# LVDS_IFC.net
KiCad netlist of a schematic drawn in Altium Designer
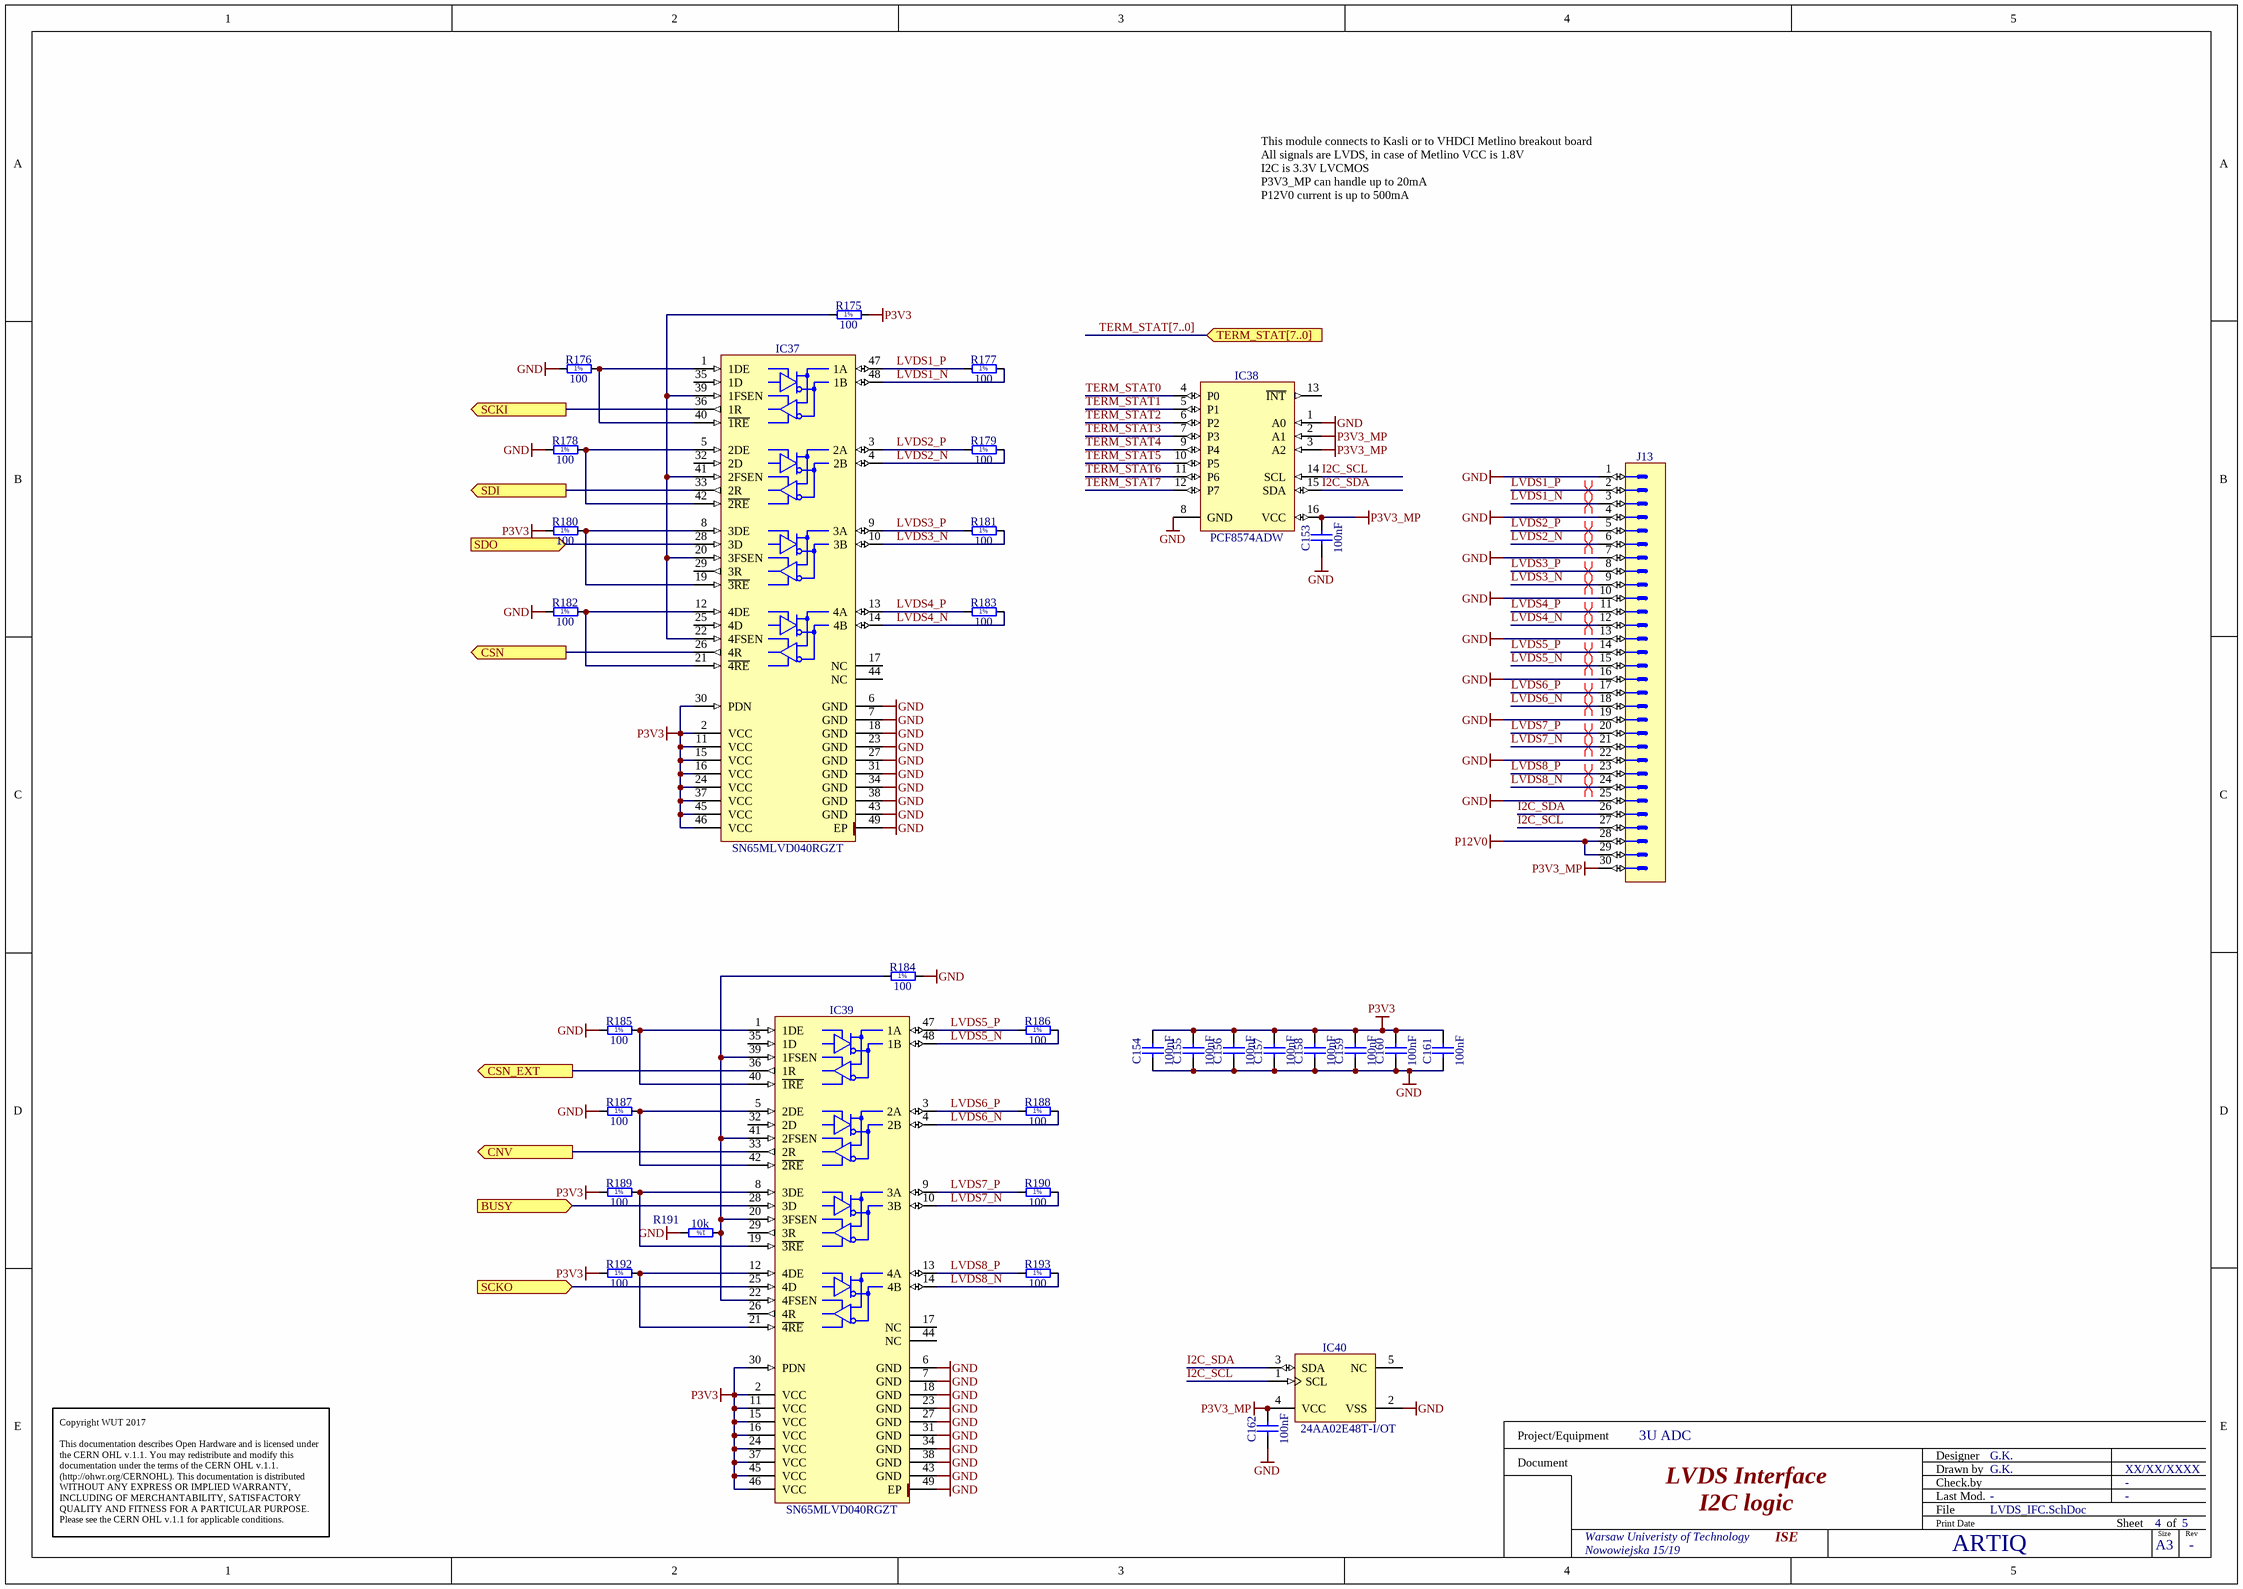
[diagram p0: LVDS_IFC.SchDoc]

(export (version "E")
  (design (tool "Eeschema 10.0.6"))
  (components
    (comp (ref "C153")
      (value "100nF")
      (footprint "CAPC1005X55N")
      (description "Non-polarised capacitor")
      (fields
        (field (name "PART NUMBER") "CC0402_100NF_16V_10%_X5R")
        (field (name "VOLTAGE") "16V")
        (field (name "AUTHOR") "CERN DEM JLC")
      )
      (libsource (lib "Capacitors") (part "Capacitor - non polarized"))
    )
    (comp (ref "C154")
      (value "100nF")
      (footprint "CAPC1005X55N")
      (description "Non-polarised capacitor")
      (fields
        (field (name "PART NUMBER") "CC0402_100NF_16V_10%_X5R")
        (field (name "VOLTAGE") "16V")
        (field (name "AUTHOR") "CERN DEM JLC")
      )
      (libsource (lib "Capacitors") (part "Capacitor - non polarized"))
    )
    (comp (ref "C155")
      (value "100nF")
      (footprint "CAPC1005X55N")
      (description "Non-polarised capacitor")
      (fields
        (field (name "PART NUMBER") "CC0402_100NF_16V_10%_X5R")
        (field (name "VOLTAGE") "16V")
        (field (name "AUTHOR") "CERN DEM JLC")
      )
      (libsource (lib "Capacitors") (part "Capacitor - non polarized"))
    )
    (comp (ref "C156")
      (value "100nF")
      (footprint "CAPC1005X55N")
      (description "Non-polarised capacitor")
      (fields
        (field (name "PART NUMBER") "CC0402_100NF_16V_10%_X5R")
        (field (name "VOLTAGE") "16V")
        (field (name "AUTHOR") "CERN DEM JLC")
      )
      (libsource (lib "Capacitors") (part "Capacitor - non polarized"))
    )
    (comp (ref "C157")
      (value "100nF")
      (footprint "CAPC1005X55N")
      (description "Non-polarised capacitor")
      (fields
        (field (name "PART NUMBER") "CC0402_100NF_16V_10%_X5R")
        (field (name "VOLTAGE") "16V")
        (field (name "AUTHOR") "CERN DEM JLC")
      )
      (libsource (lib "Capacitors") (part "Capacitor - non polarized"))
    )
    (comp (ref "C158")
      (value "100nF")
      (footprint "CAPC1005X55N")
      (description "Non-polarised capacitor")
      (fields
        (field (name "PART NUMBER") "CC0402_100NF_16V_10%_X5R")
        (field (name "VOLTAGE") "16V")
        (field (name "AUTHOR") "CERN DEM JLC")
      )
      (libsource (lib "Capacitors") (part "Capacitor - non polarized"))
    )
    (comp (ref "C159")
      (value "100nF")
      (footprint "CAPC1005X55N")
      (description "Non-polarised capacitor")
      (fields
        (field (name "PART NUMBER") "CC0402_100NF_16V_10%_X5R")
        (field (name "VOLTAGE") "16V")
        (field (name "AUTHOR") "CERN DEM JLC")
      )
      (libsource (lib "Capacitors") (part "Capacitor - non polarized"))
    )
    (comp (ref "C160")
      (value "100nF")
      (footprint "CAPC1005X55N")
      (description "Non-polarised capacitor")
      (fields
        (field (name "PART NUMBER") "CC0402_100NF_16V_10%_X5R")
        (field (name "VOLTAGE") "16V")
        (field (name "AUTHOR") "CERN DEM JLC")
      )
      (libsource (lib "Capacitors") (part "Capacitor - non polarized"))
    )
    (comp (ref "C161")
      (value "100nF")
      (footprint "CAPC1005X55N")
      (description "Non-polarised capacitor")
      (fields
        (field (name "PART NUMBER") "CC0402_100NF_16V_10%_X5R")
        (field (name "VOLTAGE") "16V")
        (field (name "AUTHOR") "CERN DEM JLC")
      )
      (libsource (lib "Capacitors") (part "Capacitor - non polarized"))
    )
    (comp (ref "C162")
      (value "100nF")
      (footprint "CAPC1005X55N")
      (description "Non-polarised capacitor")
      (fields
        (field (name "PART NUMBER") "CC0402_100NF_16V_10%_X5R")
        (field (name "VOLTAGE") "16V")
        (field (name "AUTHOR") "CERN DEM JLC")
      )
      (libsource (lib "Capacitors") (part "Capacitor - non polarized"))
    )
    (comp (ref "IC37")
      (value "SN65MLVD040RGZT")
      (footprint "QFN50P700X700X100-49N-S420")
      (description "4-Channel Half-Duplex M-LVDS Line Transceiver")
      (fields (field (name "MANUFACTURER") "TEXAS INSTRUMENTS") (field (name "AUTHOR") "CERN DEM JLC"))
      (libsource (lib "ICs And Semiconductors") (part "SN65MLVD040"))
    )
    (comp (ref "IC38")
      (value "PCF8574ADW")
      (footprint "SOIC127P1030X265-16N")
      (description "Remote 8-bit I/O Expander For I2C Bus")
      (fields (field (name "MANUFACTURER") "TEXAS INSTRUMENTS") (field (name "AUTHOR") "CERN DEM JLC"))
      (libsource (lib "ICs And Semiconductors") (part "PCF8574ADW"))
    )
    (comp (ref "IC39")
      (value "SN65MLVD040RGZT")
      (footprint "QFN50P700X700X100-49N-S420")
      (description "4-Channel Half-Duplex M-LVDS Line Transceiver")
      (fields (field (name "MANUFACTURER") "TEXAS INSTRUMENTS") (field (name "AUTHOR") "CERN DEM JLC"))
      (libsource (lib "ICs And Semiconductors") (part "SN65MLVD040"))
    )
    (comp (ref "IC40")
      (value "24AA02E48T-I/OT")
      (footprint "SOT95P280X145-5N")
      (description "1.7V-5.5V, 2K I2C Serial EEPROM With EUI-48 Node Identity")
      (fields (field (name "MANUFACTURER") "MICROCHIP TECHNOLOGY") (field (name "AUTHOR") "CERN DEM MR"))
      (libsource (lib "ICs And Semiconductors") (part "24AA02E48T-I/OT"))
    )
    (comp (ref "J13")
      (value "~")
      (footprint "3M_N2530-6002RB")
      (description "Connector 30 Male")
      (fields
        (field (name "PART NUMBER") "3M_N2530-6002RB")
        (field (name "MANUFACTURER") "3M")
        (field (name "AUTHOR") "CERN DEM JLC")
      )
      (libsource (lib "Connectors") (part "Connector 30 Male"))
    )
    (comp (ref "R175")
      (value "100")
      (footprint "RESC1005X40N")
      (description "Resistor - 1%")
      (fields
        (field (name "PART NUMBER") "R0402_100R_1%_0.1W_100PPM")
        (field (name "POWER") "0.1W")
        (field (name "AUTHOR") "CERN DEM JLC")
      )
      (libsource (lib "Resistors") (part "Resistor - 1%"))
    )
    (comp (ref "R176")
      (value "100")
      (footprint "RESC1005X40N")
      (description "Resistor - 1%")
      (fields
        (field (name "PART NUMBER") "R0402_100R_1%_0.1W_100PPM")
        (field (name "POWER") "0.1W")
        (field (name "AUTHOR") "CERN DEM JLC")
      )
      (libsource (lib "Resistors") (part "Resistor - 1%"))
    )
    (comp (ref "R177")
      (value "100")
      (footprint "RESC1005X40N")
      (description "Resistor - 1%")
      (fields
        (field (name "PART NUMBER") "R0402_100R_1%_0.1W_100PPM")
        (field (name "POWER") "0.1W")
        (field (name "AUTHOR") "CERN DEM JLC")
      )
      (libsource (lib "Resistors") (part "Resistor - 1%"))
    )
    (comp (ref "R178")
      (value "100")
      (footprint "RESC1005X40N")
      (description "Resistor - 1%")
      (fields
        (field (name "PART NUMBER") "R0402_100R_1%_0.1W_100PPM")
        (field (name "POWER") "0.1W")
        (field (name "AUTHOR") "CERN DEM JLC")
      )
      (libsource (lib "Resistors") (part "Resistor - 1%"))
    )
    (comp (ref "R179")
      (value "100")
      (footprint "RESC1005X40N")
      (description "Resistor - 1%")
      (fields
        (field (name "PART NUMBER") "R0402_100R_1%_0.1W_100PPM")
        (field (name "POWER") "0.1W")
        (field (name "AUTHOR") "CERN DEM JLC")
      )
      (libsource (lib "Resistors") (part "Resistor - 1%"))
    )
    (comp (ref "R180")
      (value "100")
      (footprint "RESC1005X40N")
      (description "Resistor - 1%")
      (fields
        (field (name "PART NUMBER") "R0402_100R_1%_0.1W_100PPM")
        (field (name "POWER") "0.1W")
        (field (name "AUTHOR") "CERN DEM JLC")
      )
      (libsource (lib "Resistors") (part "Resistor - 1%"))
    )
    (comp (ref "R181")
      (value "100")
      (footprint "RESC1005X40N")
      (description "Resistor - 1%")
      (fields
        (field (name "PART NUMBER") "R0402_100R_1%_0.1W_100PPM")
        (field (name "POWER") "0.1W")
        (field (name "AUTHOR") "CERN DEM JLC")
      )
      (libsource (lib "Resistors") (part "Resistor - 1%"))
    )
    (comp (ref "R182")
      (value "100")
      (footprint "RESC1005X40N")
      (description "Resistor - 1%")
      (fields
        (field (name "PART NUMBER") "R0402_100R_1%_0.1W_100PPM")
        (field (name "POWER") "0.1W")
        (field (name "AUTHOR") "CERN DEM JLC")
      )
      (libsource (lib "Resistors") (part "Resistor - 1%"))
    )
    (comp (ref "R183")
      (value "100")
      (footprint "RESC1005X40N")
      (description "Resistor - 1%")
      (fields
        (field (name "PART NUMBER") "R0402_100R_1%_0.1W_100PPM")
        (field (name "POWER") "0.1W")
        (field (name "AUTHOR") "CERN DEM JLC")
      )
      (libsource (lib "Resistors") (part "Resistor - 1%"))
    )
    (comp (ref "R184")
      (value "100")
      (footprint "RESC1005X40N")
      (description "Resistor - 1%")
      (fields
        (field (name "PART NUMBER") "R0402_100R_1%_0.1W_100PPM")
        (field (name "POWER") "0.1W")
        (field (name "AUTHOR") "CERN DEM JLC")
      )
      (libsource (lib "Resistors") (part "Resistor - 1%"))
    )
    (comp (ref "R185")
      (value "100")
      (footprint "RESC1005X40N")
      (description "Resistor - 1%")
      (fields
        (field (name "PART NUMBER") "R0402_100R_1%_0.1W_100PPM")
        (field (name "POWER") "0.1W")
        (field (name "AUTHOR") "CERN DEM JLC")
      )
      (libsource (lib "Resistors") (part "Resistor - 1%"))
    )
    (comp (ref "R186")
      (value "100")
      (footprint "RESC1005X40N")
      (description "Resistor - 1%")
      (fields
        (field (name "PART NUMBER") "R0402_100R_1%_0.1W_100PPM")
        (field (name "POWER") "0.1W")
        (field (name "AUTHOR") "CERN DEM JLC")
      )
      (libsource (lib "Resistors") (part "Resistor - 1%"))
    )
    (comp (ref "R187")
      (value "100")
      (footprint "RESC1005X40N")
      (description "Resistor - 1%")
      (fields
        (field (name "PART NUMBER") "R0402_100R_1%_0.1W_100PPM")
        (field (name "POWER") "0.1W")
        (field (name "AUTHOR") "CERN DEM JLC")
      )
      (libsource (lib "Resistors") (part "Resistor - 1%"))
    )
    (comp (ref "R188")
      (value "100")
      (footprint "RESC1005X40N")
      (description "Resistor - 1%")
      (fields
        (field (name "PART NUMBER") "R0402_100R_1%_0.1W_100PPM")
        (field (name "POWER") "0.1W")
        (field (name "AUTHOR") "CERN DEM JLC")
      )
      (libsource (lib "Resistors") (part "Resistor - 1%"))
    )
    (comp (ref "R189")
      (value "100")
      (footprint "RESC1005X40N")
      (description "Resistor - 1%")
      (fields
        (field (name "PART NUMBER") "R0402_100R_1%_0.1W_100PPM")
        (field (name "POWER") "0.1W")
        (field (name "AUTHOR") "CERN DEM JLC")
      )
      (libsource (lib "Resistors") (part "Resistor - 1%"))
    )
    (comp (ref "R190")
      (value "100")
      (footprint "RESC1005X40N")
      (description "Resistor - 1%")
      (fields
        (field (name "PART NUMBER") "R0402_100R_1%_0.1W_100PPM")
        (field (name "POWER") "0.1W")
        (field (name "AUTHOR") "CERN DEM JLC")
      )
      (libsource (lib "Resistors") (part "Resistor - 1%"))
    )
    (comp (ref "R191")
      (value "10k")
      (footprint "RESC1005X40N")
      (description "Resistor - 1%")
      (fields
        (field (name "PART NUMBER") "R0402_10K_1%_0.0625W_100PPM")
        (field (name "POWER") "0.0625W")
        (field (name "AUTHOR") "CERN DEM JLC")
      )
      (libsource (lib "Resistors") (part "Resistor - 1%"))
    )
    (comp (ref "R192")
      (value "100")
      (footprint "RESC1005X40N")
      (description "Resistor - 1%")
      (fields
        (field (name "PART NUMBER") "R0402_100R_1%_0.1W_100PPM")
        (field (name "POWER") "0.1W")
        (field (name "AUTHOR") "CERN DEM JLC")
      )
      (libsource (lib "Resistors") (part "Resistor - 1%"))
    )
    (comp (ref "R193")
      (value "100")
      (footprint "RESC1005X40N")
      (description "Resistor - 1%")
      (fields
        (field (name "PART NUMBER") "R0402_100R_1%_0.1W_100PPM")
        (field (name "POWER") "0.1W")
        (field (name "AUTHOR") "CERN DEM JLC")
      )
      (libsource (lib "Resistors") (part "Resistor - 1%"))
    )
  )
  (nets
    (net (code "1") (name "/BUSY") (class "Default")
      (node (ref "IC39") (pin "28") (pinfunction "3D_28") (pintype "input"))
    )
    (net (code "2") (name "/CNV") (class "Default")
      (node (ref "IC39") (pin "33") (pinfunction "2R_33") (pintype "output"))
    )
    (net (code "3") (name "/CSN") (class "Default")
      (node (ref "IC37") (pin "26") (pinfunction "4R_26") (pintype "output"))
    )
    (net (code "4") (name "/CSN_EXT") (class "Default")
      (node (ref "IC39") (pin "36") (pinfunction "1R_36") (pintype "output"))
    )
    (net (code "5") (name "/I2C_SCL") (class "Default")
      (node (ref "IC38") (pin "14") (pinfunction "SCL_14") (pintype "input"))
      (node (ref "IC40") (pin "1") (pinfunction "SCL_1") (pintype "input"))
      (node (ref "J13") (pin "27") (pinfunction "27_27") (pintype "bidirectional"))
    )
    (net (code "6") (name "/I2C_SDA") (class "Default")
      (node (ref "IC38") (pin "15") (pinfunction "SDA_15") (pintype "bidirectional"))
      (node (ref "IC40") (pin "3") (pinfunction "SDA_3") (pintype "bidirectional"))
      (node (ref "J13") (pin "26") (pinfunction "26_26") (pintype "bidirectional"))
    )
    (net (code "7") (name "/LVDS1_N") (class "Default")
      (node (ref "IC37") (pin "48") (pinfunction "1B_48") (pintype "bidirectional"))
      (node (ref "J13") (pin "3") (pinfunction "3_3") (pintype "bidirectional"))
      (node (ref "R177") (pin "2") (pinfunction "2_2") (pintype "passive"))
    )
    (net (code "8") (name "/LVDS1_P") (class "Default")
      (node (ref "IC37") (pin "47") (pinfunction "1A_47") (pintype "bidirectional"))
      (node (ref "J13") (pin "2") (pinfunction "2_2") (pintype "bidirectional"))
      (node (ref "R177") (pin "1") (pinfunction "1_1") (pintype "passive"))
    )
    (net (code "9") (name "/LVDS2_N") (class "Default")
      (node (ref "IC37") (pin "4") (pinfunction "2B_4") (pintype "bidirectional"))
      (node (ref "J13") (pin "6") (pinfunction "6_6") (pintype "bidirectional"))
      (node (ref "R179") (pin "2") (pinfunction "2_2") (pintype "passive"))
    )
    (net (code "10") (name "/LVDS2_P") (class "Default")
      (node (ref "IC37") (pin "3") (pinfunction "2A_3") (pintype "bidirectional"))
      (node (ref "J13") (pin "5") (pinfunction "5_5") (pintype "bidirectional"))
      (node (ref "R179") (pin "1") (pinfunction "1_1") (pintype "passive"))
    )
    (net (code "11") (name "/LVDS3_N") (class "Default")
      (node (ref "IC37") (pin "10") (pinfunction "3B_10") (pintype "bidirectional"))
      (node (ref "J13") (pin "9") (pinfunction "9_9") (pintype "bidirectional"))
      (node (ref "R181") (pin "2") (pinfunction "2_2") (pintype "passive"))
    )
    (net (code "12") (name "/LVDS3_P") (class "Default")
      (node (ref "IC37") (pin "9") (pinfunction "3A_9") (pintype "bidirectional"))
      (node (ref "J13") (pin "8") (pinfunction "8_8") (pintype "bidirectional"))
      (node (ref "R181") (pin "1") (pinfunction "1_1") (pintype "passive"))
    )
    (net (code "13") (name "/LVDS4_N") (class "Default")
      (node (ref "IC37") (pin "14") (pinfunction "4B_14") (pintype "bidirectional"))
      (node (ref "J13") (pin "12") (pinfunction "12_12") (pintype "bidirectional"))
      (node (ref "R183") (pin "2") (pinfunction "2_2") (pintype "passive"))
    )
    (net (code "14") (name "/LVDS4_P") (class "Default")
      (node (ref "IC37") (pin "13") (pinfunction "4A_13") (pintype "bidirectional"))
      (node (ref "J13") (pin "11") (pinfunction "11_11") (pintype "bidirectional"))
      (node (ref "R183") (pin "1") (pinfunction "1_1") (pintype "passive"))
    )
    (net (code "15") (name "/LVDS5_N") (class "Default")
      (node (ref "IC39") (pin "48") (pinfunction "1B_48") (pintype "bidirectional"))
      (node (ref "J13") (pin "15") (pinfunction "15_15") (pintype "bidirectional"))
      (node (ref "R186") (pin "2") (pinfunction "2_2") (pintype "passive"))
    )
    (net (code "16") (name "/LVDS5_P") (class "Default")
      (node (ref "IC39") (pin "47") (pinfunction "1A_47") (pintype "bidirectional"))
      (node (ref "J13") (pin "14") (pinfunction "14_14") (pintype "bidirectional"))
      (node (ref "R186") (pin "1") (pinfunction "1_1") (pintype "passive"))
    )
    (net (code "17") (name "/LVDS6_N") (class "Default")
      (node (ref "IC39") (pin "4") (pinfunction "2B_4") (pintype "bidirectional"))
      (node (ref "J13") (pin "18") (pinfunction "18_18") (pintype "bidirectional"))
      (node (ref "R188") (pin "2") (pinfunction "2_2") (pintype "passive"))
    )
    (net (code "18") (name "/LVDS6_P") (class "Default")
      (node (ref "IC39") (pin "3") (pinfunction "2A_3") (pintype "bidirectional"))
      (node (ref "J13") (pin "17") (pinfunction "17_17") (pintype "bidirectional"))
      (node (ref "R188") (pin "1") (pinfunction "1_1") (pintype "passive"))
    )
    (net (code "19") (name "/LVDS7_N") (class "Default")
      (node (ref "IC39") (pin "10") (pinfunction "3B_10") (pintype "bidirectional"))
      (node (ref "J13") (pin "21") (pinfunction "21_21") (pintype "bidirectional"))
      (node (ref "R190") (pin "2") (pinfunction "2_2") (pintype "passive"))
    )
    (net (code "20") (name "/LVDS7_P") (class "Default")
      (node (ref "IC39") (pin "9") (pinfunction "3A_9") (pintype "bidirectional"))
      (node (ref "J13") (pin "20") (pinfunction "20_20") (pintype "bidirectional"))
      (node (ref "R190") (pin "1") (pinfunction "1_1") (pintype "passive"))
    )
    (net (code "21") (name "/LVDS8_N") (class "Default")
      (node (ref "IC39") (pin "14") (pinfunction "4B_14") (pintype "bidirectional"))
      (node (ref "J13") (pin "24") (pinfunction "24_24") (pintype "bidirectional"))
      (node (ref "R193") (pin "2") (pinfunction "2_2") (pintype "passive"))
    )
    (net (code "22") (name "/LVDS8_P") (class "Default")
      (node (ref "IC39") (pin "13") (pinfunction "4A_13") (pintype "bidirectional"))
      (node (ref "J13") (pin "23") (pinfunction "23_23") (pintype "bidirectional"))
      (node (ref "R193") (pin "1") (pinfunction "1_1") (pintype "passive"))
    )
    (net (code "23") (name "/SCKI") (class "Default")
      (node (ref "IC37") (pin "36") (pinfunction "1R_36") (pintype "output"))
    )
    (net (code "24") (name "/SCKO") (class "Default")
      (node (ref "IC39") (pin "25") (pinfunction "4D_25") (pintype "input"))
    )
    (net (code "25") (name "/SDI") (class "Default")
      (node (ref "IC37") (pin "33") (pinfunction "2R_33") (pintype "output"))
    )
    (net (code "26") (name "/SDO") (class "Default")
      (node (ref "IC37") (pin "28") (pinfunction "3D_28") (pintype "input"))
    )
    (net (code "27") (name "/TERM_STAT0") (class "Default")
      (node (ref "IC38") (pin "4") (pinfunction "P0_4") (pintype "bidirectional"))
    )
    (net (code "28") (name "/TERM_STAT1") (class "Default")
      (node (ref "IC38") (pin "5") (pinfunction "P1_5") (pintype "bidirectional"))
    )
    (net (code "29") (name "/TERM_STAT2") (class "Default")
      (node (ref "IC38") (pin "6") (pinfunction "P2_6") (pintype "bidirectional"))
    )
    (net (code "30") (name "/TERM_STAT3") (class "Default")
      (node (ref "IC38") (pin "7") (pinfunction "P3_7") (pintype "bidirectional"))
    )
    (net (code "31") (name "/TERM_STAT4") (class "Default")
      (node (ref "IC38") (pin "9") (pinfunction "P4_9") (pintype "bidirectional"))
    )
    (net (code "32") (name "/TERM_STAT5") (class "Default")
      (node (ref "IC38") (pin "10") (pinfunction "P5_10") (pintype "bidirectional"))
    )
    (net (code "33") (name "/TERM_STAT6") (class "Default")
      (node (ref "IC38") (pin "11") (pinfunction "P6_11") (pintype "bidirectional"))
    )
    (net (code "34") (name "/TERM_STAT7") (class "Default")
      (node (ref "IC38") (pin "12") (pinfunction "P7_12") (pintype "bidirectional"))
    )
    (net (code "36") (name "GND") (class "Default")
      (node (ref "C153") (pin "1") (pinfunction "1_1") (pintype "passive"))
      (node (ref "C154") (pin "1") (pinfunction "1_1") (pintype "passive"))
      (node (ref "C155") (pin "1") (pinfunction "1_1") (pintype "passive"))
      (node (ref "C156") (pin "1") (pinfunction "1_1") (pintype "passive"))
      (node (ref "C157") (pin "1") (pinfunction "1_1") (pintype "passive"))
      (node (ref "C158") (pin "1") (pinfunction "1_1") (pintype "passive"))
      (node (ref "C159") (pin "1") (pinfunction "1_1") (pintype "passive"))
      (node (ref "C160") (pin "1") (pinfunction "1_1") (pintype "passive"))
      (node (ref "C161") (pin "1") (pinfunction "1_1") (pintype "passive"))
      (node (ref "C162") (pin "1") (pinfunction "1_1") (pintype "passive"))
      (node (ref "IC37") (pin "18") (pinfunction "GND_18") (pintype "power_in"))
      (node (ref "IC37") (pin "23") (pinfunction "GND_23") (pintype "power_in"))
      (node (ref "IC37") (pin "27") (pinfunction "GND_27") (pintype "power_in"))
      (node (ref "IC37") (pin "31") (pinfunction "GND_31") (pintype "power_in"))
      (node (ref "IC37") (pin "34") (pinfunction "GND_34") (pintype "power_in"))
      (node (ref "IC37") (pin "38") (pinfunction "GND_38") (pintype "power_in"))
      (node (ref "IC37") (pin "43") (pinfunction "GND_43") (pintype "power_in"))
      (node (ref "IC37") (pin "49") (pinfunction "EP_49") (pintype "power_in"))
      (node (ref "IC37") (pin "6") (pinfunction "GND_6") (pintype "power_in"))
      (node (ref "IC37") (pin "7") (pinfunction "GND_7") (pintype "power_in"))
      (node (ref "IC38") (pin "1") (pinfunction "A0_1") (pintype "input"))
      (node (ref "IC38") (pin "8") (pinfunction "GND_8") (pintype "power_in"))
      (node (ref "IC39") (pin "18") (pinfunction "GND_18") (pintype "power_in"))
      (node (ref "IC39") (pin "23") (pinfunction "GND_23") (pintype "power_in"))
      (node (ref "IC39") (pin "27") (pinfunction "GND_27") (pintype "power_in"))
      (node (ref "IC39") (pin "31") (pinfunction "GND_31") (pintype "power_in"))
      (node (ref "IC39") (pin "34") (pinfunction "GND_34") (pintype "power_in"))
      (node (ref "IC39") (pin "38") (pinfunction "GND_38") (pintype "power_in"))
      (node (ref "IC39") (pin "43") (pinfunction "GND_43") (pintype "power_in"))
      (node (ref "IC39") (pin "49") (pinfunction "EP_49") (pintype "power_in"))
      (node (ref "IC39") (pin "6") (pinfunction "GND_6") (pintype "power_in"))
      (node (ref "IC39") (pin "7") (pinfunction "GND_7") (pintype "power_in"))
      (node (ref "IC40") (pin "2") (pinfunction "VSS_2") (pintype "power_in"))
      (node (ref "J13") (pin "1") (pinfunction "1_1") (pintype "bidirectional"))
      (node (ref "J13") (pin "10") (pinfunction "10_10") (pintype "bidirectional"))
      (node (ref "J13") (pin "13") (pinfunction "13_13") (pintype "bidirectional"))
      (node (ref "J13") (pin "16") (pinfunction "16_16") (pintype "bidirectional"))
      (node (ref "J13") (pin "19") (pinfunction "19_19") (pintype "bidirectional"))
      (node (ref "J13") (pin "22") (pinfunction "22_22") (pintype "bidirectional"))
      (node (ref "J13") (pin "25") (pinfunction "25_25") (pintype "bidirectional"))
      (node (ref "J13") (pin "4") (pinfunction "4_4") (pintype "bidirectional"))
      (node (ref "J13") (pin "7") (pinfunction "7_7") (pintype "bidirectional"))
      (node (ref "R176") (pin "1") (pinfunction "1_1") (pintype "passive"))
      (node (ref "R178") (pin "1") (pinfunction "1_1") (pintype "passive"))
      (node (ref "R182") (pin "1") (pinfunction "1_1") (pintype "passive"))
      (node (ref "R184") (pin "2") (pinfunction "2_2") (pintype "passive"))
      (node (ref "R185") (pin "1") (pinfunction "1_1") (pintype "passive"))
      (node (ref "R187") (pin "1") (pinfunction "1_1") (pintype "passive"))
      (node (ref "R191") (pin "2") (pinfunction "2_2") (pintype "passive"))
    )
    (net (code "37") (name "Net-(IC37-1DE)") (class "Default")
      (node (ref "IC37") (pin "1") (pinfunction "1DE_1") (pintype "input"))
      (node (ref "IC37") (pin "40") (pinfunction "~{1RE}_40") (pintype "input"))
      (node (ref "R176") (pin "2") (pinfunction "2_2") (pintype "passive"))
    )
    (net (code "38") (name "Net-(IC37-1FSEN)") (class "Default")
      (node (ref "IC37") (pin "20") (pinfunction "3FSEN_20") (pintype "input"))
      (node (ref "IC37") (pin "22") (pinfunction "4FSEN_22") (pintype "input"))
      (node (ref "IC37") (pin "39") (pinfunction "1FSEN_39") (pintype "input"))
      (node (ref "IC37") (pin "41") (pinfunction "2FSEN_41") (pintype "input"))
      (node (ref "R175") (pin "1") (pinfunction "1_1") (pintype "passive"))
    )
    (net (code "39") (name "Net-(IC37-2DE)") (class "Default")
      (node (ref "IC37") (pin "42") (pinfunction "~{2RE}_42") (pintype "input"))
      (node (ref "IC37") (pin "5") (pinfunction "2DE_5") (pintype "input"))
      (node (ref "R178") (pin "2") (pinfunction "2_2") (pintype "passive"))
    )
    (net (code "40") (name "Net-(IC37-3DE)") (class "Default")
      (node (ref "IC37") (pin "19") (pinfunction "~{3RE}_19") (pintype "input"))
      (node (ref "IC37") (pin "8") (pinfunction "3DE_8") (pintype "input"))
      (node (ref "R180") (pin "2") (pinfunction "2_2") (pintype "passive"))
    )
    (net (code "41") (name "Net-(IC37-4DE)") (class "Default")
      (node (ref "IC37") (pin "12") (pinfunction "4DE_12") (pintype "input"))
      (node (ref "IC37") (pin "21") (pinfunction "~{4RE}_21") (pintype "input"))
      (node (ref "R182") (pin "2") (pinfunction "2_2") (pintype "passive"))
    )
    (net (code "42") (name "Net-(IC39-1DE)") (class "Default")
      (node (ref "IC39") (pin "1") (pinfunction "1DE_1") (pintype "input"))
      (node (ref "IC39") (pin "40") (pinfunction "~{1RE}_40") (pintype "input"))
      (node (ref "R185") (pin "2") (pinfunction "2_2") (pintype "passive"))
    )
    (net (code "43") (name "Net-(IC39-1FSEN)") (class "Default")
      (node (ref "IC39") (pin "20") (pinfunction "3FSEN_20") (pintype "input"))
      (node (ref "IC39") (pin "22") (pinfunction "4FSEN_22") (pintype "input"))
      (node (ref "IC39") (pin "39") (pinfunction "1FSEN_39") (pintype "input"))
      (node (ref "IC39") (pin "41") (pinfunction "2FSEN_41") (pintype "input"))
      (node (ref "R184") (pin "1") (pinfunction "1_1") (pintype "passive"))
      (node (ref "R191") (pin "1") (pinfunction "1_1") (pintype "passive"))
    )
    (net (code "44") (name "Net-(IC39-2DE)") (class "Default")
      (node (ref "IC39") (pin "42") (pinfunction "~{2RE}_42") (pintype "input"))
      (node (ref "IC39") (pin "5") (pinfunction "2DE_5") (pintype "input"))
      (node (ref "R187") (pin "2") (pinfunction "2_2") (pintype "passive"))
    )
    (net (code "45") (name "Net-(IC39-3DE)") (class "Default")
      (node (ref "IC39") (pin "19") (pinfunction "~{3RE}_19") (pintype "input"))
      (node (ref "IC39") (pin "8") (pinfunction "3DE_8") (pintype "input"))
      (node (ref "R189") (pin "2") (pinfunction "2_2") (pintype "passive"))
    )
    (net (code "46") (name "Net-(IC39-4DE)") (class "Default")
      (node (ref "IC39") (pin "12") (pinfunction "4DE_12") (pintype "input"))
      (node (ref "IC39") (pin "21") (pinfunction "~{4RE}_21") (pintype "input"))
      (node (ref "R192") (pin "2") (pinfunction "2_2") (pintype "passive"))
    )
    (net (code "47") (name "P3V3") (class "Default")
      (node (ref "C154") (pin "2") (pinfunction "2_2") (pintype "passive"))
      (node (ref "C155") (pin "2") (pinfunction "2_2") (pintype "passive"))
      (node (ref "C156") (pin "2") (pinfunction "2_2") (pintype "passive"))
      (node (ref "C157") (pin "2") (pinfunction "2_2") (pintype "passive"))
      (node (ref "C158") (pin "2") (pinfunction "2_2") (pintype "passive"))
      (node (ref "C159") (pin "2") (pinfunction "2_2") (pintype "passive"))
      (node (ref "C160") (pin "2") (pinfunction "2_2") (pintype "passive"))
      (node (ref "C161") (pin "2") (pinfunction "2_2") (pintype "passive"))
      (node (ref "IC37") (pin "11") (pinfunction "VCC_11") (pintype "power_in"))
      (node (ref "IC37") (pin "15") (pinfunction "VCC_15") (pintype "power_in"))
      (node (ref "IC37") (pin "16") (pinfunction "VCC_16") (pintype "power_in"))
      (node (ref "IC37") (pin "2") (pinfunction "VCC_2") (pintype "power_in"))
      (node (ref "IC37") (pin "24") (pinfunction "VCC_24") (pintype "power_in"))
      (node (ref "IC37") (pin "30") (pinfunction "PDN_30") (pintype "input"))
      (node (ref "IC37") (pin "37") (pinfunction "VCC_37") (pintype "power_in"))
      (node (ref "IC37") (pin "45") (pinfunction "VCC_45") (pintype "power_in"))
      (node (ref "IC37") (pin "46") (pinfunction "VCC_46") (pintype "power_in"))
      (node (ref "IC39") (pin "11") (pinfunction "VCC_11") (pintype "power_in"))
      (node (ref "IC39") (pin "15") (pinfunction "VCC_15") (pintype "power_in"))
      (node (ref "IC39") (pin "16") (pinfunction "VCC_16") (pintype "power_in"))
      (node (ref "IC39") (pin "2") (pinfunction "VCC_2") (pintype "power_in"))
      (node (ref "IC39") (pin "24") (pinfunction "VCC_24") (pintype "power_in"))
      (node (ref "IC39") (pin "30") (pinfunction "PDN_30") (pintype "input"))
      (node (ref "IC39") (pin "37") (pinfunction "VCC_37") (pintype "power_in"))
      (node (ref "IC39") (pin "45") (pinfunction "VCC_45") (pintype "power_in"))
      (node (ref "IC39") (pin "46") (pinfunction "VCC_46") (pintype "power_in"))
      (node (ref "R175") (pin "2") (pinfunction "2_2") (pintype "passive"))
      (node (ref "R180") (pin "1") (pinfunction "1_1") (pintype "passive"))
      (node (ref "R189") (pin "1") (pinfunction "1_1") (pintype "passive"))
      (node (ref "R192") (pin "1") (pinfunction "1_1") (pintype "passive"))
    )
    (net (code "48") (name "P3V3_MP") (class "Default")
      (node (ref "C153") (pin "2") (pinfunction "2_2") (pintype "passive"))
      (node (ref "C162") (pin "2") (pinfunction "2_2") (pintype "passive"))
      (node (ref "IC38") (pin "16") (pinfunction "VCC_16") (pintype "bidirectional"))
      (node (ref "IC38") (pin "2") (pinfunction "A1_2") (pintype "input"))
      (node (ref "IC38") (pin "3") (pinfunction "A2_3") (pintype "input"))
      (node (ref "IC40") (pin "4") (pinfunction "VCC_4") (pintype "power_in"))
      (node (ref "J13") (pin "30") (pinfunction "30_30") (pintype "bidirectional"))
    )
    (net (code "49") (name "P12V0") (class "Default")
      (node (ref "J13") (pin "28") (pinfunction "28_28") (pintype "bidirectional"))
      (node (ref "J13") (pin "29") (pinfunction "29_29") (pintype "bidirectional"))
    )
    (net (code "50") (name "unconnected-(IC37-1D-Pad35)") (class "Default")
      (node (ref "IC37") (pin "35") (pinfunction "1D_35") (pintype "input"))
    )
    (net (code "51") (name "unconnected-(IC37-2D-Pad32)") (class "Default")
      (node (ref "IC37") (pin "32") (pinfunction "2D_32") (pintype "input"))
    )
    (net (code "52") (name "unconnected-(IC37-3R-Pad29)") (class "Default")
      (node (ref "IC37") (pin "29") (pinfunction "3R_29") (pintype "output"))
    )
    (net (code "53") (name "unconnected-(IC37-4D-Pad25)") (class "Default")
      (node (ref "IC37") (pin "25") (pinfunction "4D_25") (pintype "input"))
    )
    (net (code "54") (name "unconnected-(IC37-NC-Pad17)") (class "Default")
      (node (ref "IC37") (pin "17") (pinfunction "NC_17") (pintype "passive"))
    )
    (net (code "55") (name "unconnected-(IC37-NC-Pad44)") (class "Default")
      (node (ref "IC37") (pin "44") (pinfunction "NC_44") (pintype "passive"))
    )
    (net (code "56") (name "unconnected-(IC38-~{INT}-Pad13)") (class "Default")
      (node (ref "IC38") (pin "13") (pinfunction "~{INT}_13") (pintype "output"))
    )
    (net (code "57") (name "unconnected-(IC39-1D-Pad35)") (class "Default")
      (node (ref "IC39") (pin "35") (pinfunction "1D_35") (pintype "input"))
    )
    (net (code "58") (name "unconnected-(IC39-2D-Pad32)") (class "Default")
      (node (ref "IC39") (pin "32") (pinfunction "2D_32") (pintype "input"))
    )
    (net (code "59") (name "unconnected-(IC39-3R-Pad29)") (class "Default")
      (node (ref "IC39") (pin "29") (pinfunction "3R_29") (pintype "output"))
    )
    (net (code "60") (name "unconnected-(IC39-4R-Pad26)") (class "Default")
      (node (ref "IC39") (pin "26") (pinfunction "4R_26") (pintype "output"))
    )
    (net (code "61") (name "unconnected-(IC39-NC-Pad17)") (class "Default")
      (node (ref "IC39") (pin "17") (pinfunction "NC_17") (pintype "passive"))
    )
    (net (code "62") (name "unconnected-(IC39-NC-Pad44)") (class "Default")
      (node (ref "IC39") (pin "44") (pinfunction "NC_44") (pintype "passive"))
    )
    (net (code "63") (name "unconnected-(IC40-NC-Pad5)") (class "Default")
      (node (ref "IC40") (pin "5") (pinfunction "NC_5") (pintype "passive"))
    )
  )
)
